# simple-loop.net
KiCad netlist of a schematic drawn in EAGLE
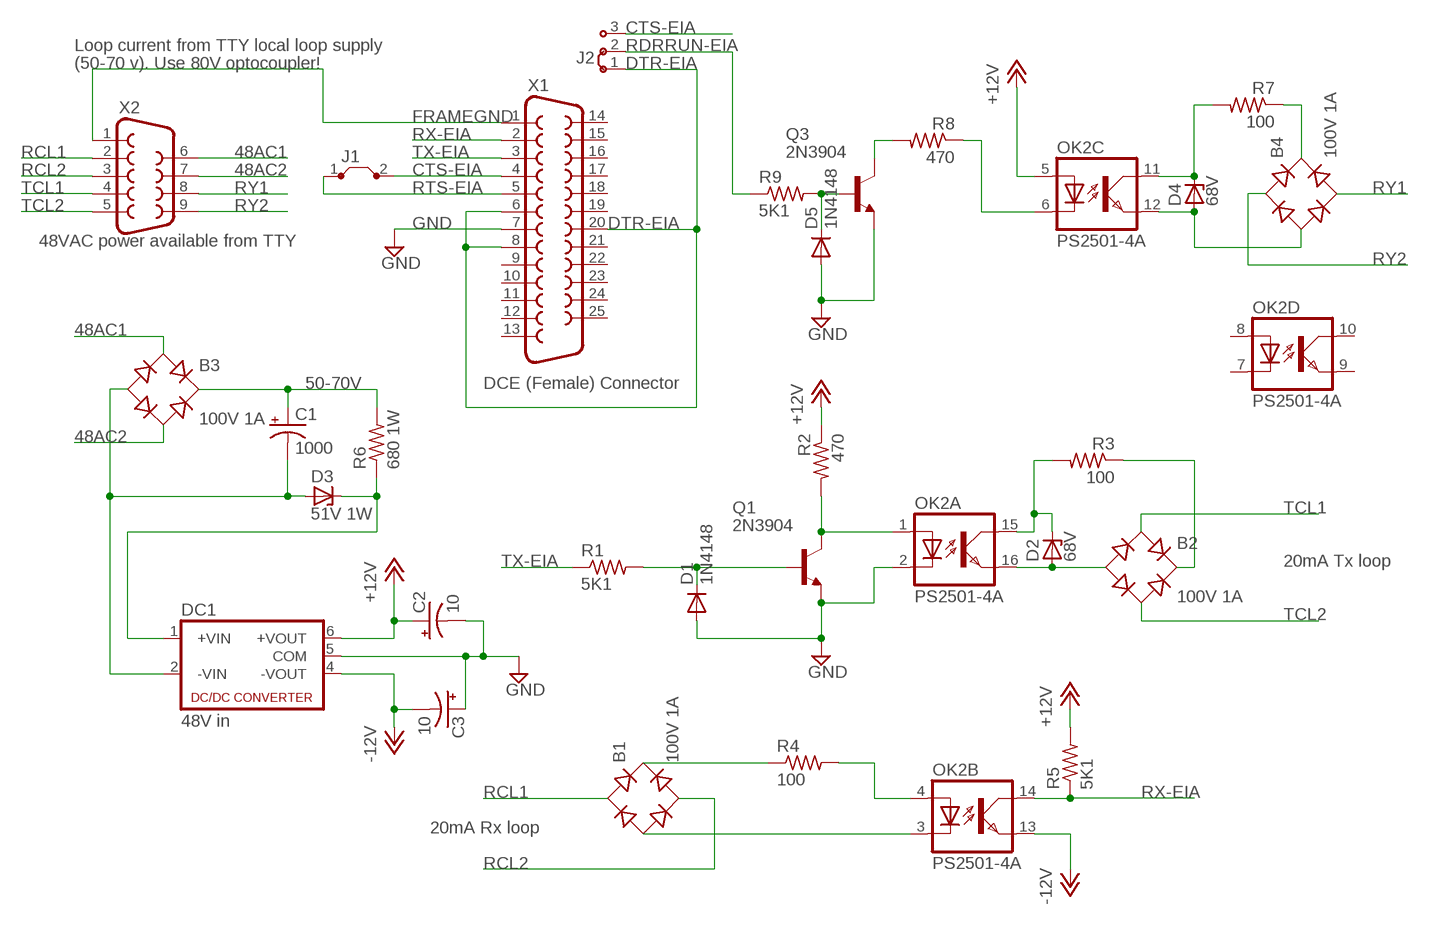
[diagram p0: schematic, sheet 1]

(export (version "E")
  (design (tool "Eeschema 10.0.6"))
  (components
    (comp (ref "B1")
      (value "100V 1A")
      (footprint "eagle-import:RB1A")
      (libsource (lib "eagle-import") (part "RB1A"))
    )
    (comp (ref "B2")
      (value "100V 1A")
      (footprint "eagle-import:RB1A")
      (libsource (lib "eagle-import") (part "RB1A"))
    )
    (comp (ref "B3")
      (value "100V 1A")
      (footprint "eagle-import:RB1A")
      (libsource (lib "eagle-import") (part "RB1A"))
    )
    (comp (ref "B4")
      (value "100V 1A")
      (footprint "eagle-import:RB1A")
      (libsource (lib "eagle-import") (part "RB1A"))
    )
    (comp (ref "C1")
      (value "1000")
      (footprint "eagle-import:E7,5-18")
      (libsource (lib "eagle-import") (part "CPOL-USE7.5-18"))
    )
    (comp (ref "C2")
      (value "10")
      (footprint "eagle-import:B45181A")
      (libsource (lib "eagle-import") (part "CPOL-USB45181A"))
    )
    (comp (ref "C3")
      (value "10")
      (footprint "eagle-import:B45181A")
      (libsource (lib "eagle-import") (part "CPOL-USB45181A"))
    )
    (comp (ref "D1")
      (value "1N4148")
      (footprint "eagle-import:DO35-10")
      (libsource (lib "eagle-import") (part "1N4148DO35-10"))
    )
    (comp (ref "D2")
      (value "68V")
      (footprint "eagle-import:DO41Z10")
      (libsource (lib "eagle-import") (part "ZENER-DIODEDO41Z10"))
    )
    (comp (ref "D3")
      (value "51V 1W")
      (footprint "eagle-import:DO41Z10")
      (libsource (lib "eagle-import") (part "ZENER-DIODEDO41Z10"))
    )
    (comp (ref "D4")
      (value "68V")
      (footprint "eagle-import:DO41Z10")
      (libsource (lib "eagle-import") (part "ZENER-DIODEDO41Z10"))
    )
    (comp (ref "D5")
      (value "1N4148")
      (footprint "eagle-import:DO35-10")
      (libsource (lib "eagle-import") (part "1N4148DO35-10"))
    )
    (comp (ref "DC1")
      (value "48V in")
      (footprint "eagle-import:NMA")
      (fields (field (name "MF") "C & D TECHNOLOGIES, INC") (field (name "MPN") "NMA0515SC"))
      (libsource (lib "eagle-import") (part "NMA"))
    )
    (comp (ref "J1")
      (value "J5MM")
      (footprint "eagle-import:05")
      (libsource (lib "eagle-import") (part "J5MM"))
    )
    (comp (ref "J2")
      (value "J2X5MM")
      (footprint "eagle-import:05C")
      (libsource (lib "eagle-import") (part "J2X5MM"))
    )
    (comp (ref "OK2")
      (value "PS2501-4A")
      (footprint "eagle-import:DIL16")
      (fields (field (name "MF") "VISHAY/TELEFUNKEN") (field (name "MPN") "ILQ1"))
      (libsource (lib "eagle-import") (part "ILQ1"))
    )
    (comp (ref "Q1")
      (value "2N3904")
      (footprint "eagle-import:TO92")
      (libsource (lib "eagle-import") (part "2N3904"))
    )
    (comp (ref "Q3")
      (value "2N3904")
      (footprint "eagle-import:TO92")
      (libsource (lib "eagle-import") (part "2N3904"))
    )
    (comp (ref "R1")
      (value "5K1")
      (footprint "eagle-import:0207_10")
      (libsource (lib "eagle-import") (part "R-US_0207/10"))
    )
    (comp (ref "R2")
      (value "470")
      (footprint "eagle-import:0207_10")
      (libsource (lib "eagle-import") (part "R-US_0207/10"))
    )
    (comp (ref "R3")
      (value "100")
      (footprint "eagle-import:0207_10")
      (libsource (lib "eagle-import") (part "R-US_0207/10"))
    )
    (comp (ref "R4")
      (value "100")
      (footprint "eagle-import:0207_10")
      (libsource (lib "eagle-import") (part "R-US_0207/10"))
    )
    (comp (ref "R5")
      (value "5K1")
      (footprint "eagle-import:0207_10")
      (libsource (lib "eagle-import") (part "R-US_0207/10"))
    )
    (comp (ref "R6")
      (value "680 1W")
      (footprint "eagle-import:0617_17")
      (libsource (lib "eagle-import") (part "R-US_0617/17"))
    )
    (comp (ref "R7")
      (value "100")
      (footprint "eagle-import:0207_10")
      (libsource (lib "eagle-import") (part "R-US_0207/10"))
    )
    (comp (ref "R8")
      (value "470")
      (footprint "eagle-import:0207_10")
      (libsource (lib "eagle-import") (part "R-US_0207/10"))
    )
    (comp (ref "R9")
      (value "5K1")
      (footprint "eagle-import:0207_10")
      (libsource (lib "eagle-import") (part "R-US_0207/10"))
    )
    (comp (ref "X1")
      (value "F25H")
      (footprint "eagle-import:F25H")
      (libsource (lib "eagle-import") (part "F25H"))
    )
    (comp (ref "X2")
      (value "F09H")
      (footprint "eagle-import:F09H")
      (libsource (lib "eagle-import") (part "F09H"))
    )
  )
  (nets
    (net (code "1") (name "+12V") (class "Default")
      (node (ref "C2") (pin "+") (pinfunction "+_+") (pintype "passive"))
      (node (ref "DC1") (pin "6") (pinfunction "+VOUT_6") (pintype "passive"))
      (node (ref "OK2") (pin "5") (pinfunction "A_5") (pintype "passive"))
      (node (ref "R2") (pin "1") (pinfunction "1_1") (pintype "passive"))
      (node (ref "R5") (pin "2") (pinfunction "2_2") (pintype "passive"))
    )
    (net (code "2") (name "-12V") (class "Default")
      (node (ref "C3") (pin "-") (pinfunction "-_-") (pintype "passive"))
      (node (ref "DC1") (pin "4") (pinfunction "-VOUT_4") (pintype "passive"))
      (node (ref "OK2") (pin "13") (pinfunction "EMIT_13") (pintype "passive"))
    )
    (net (code "3") (name "/48AC1") (class "Default")
      (node (ref "B3") (pin "AC1") (pinfunction "AC1_AC1") (pintype "passive"))
      (node (ref "X2") (pin "6") (pinfunction "6_6") (pintype "passive"))
    )
    (net (code "4") (name "/48AC2") (class "Default")
      (node (ref "B3") (pin "AC2") (pinfunction "AC2_AC2") (pintype "passive"))
      (node (ref "X2") (pin "7") (pinfunction "7_7") (pintype "passive"))
    )
    (net (code "5") (name "/50-70V") (class "Default")
      (node (ref "B3") (pin "+") (pinfunction "+_+") (pintype "passive"))
      (node (ref "C1") (pin "+") (pinfunction "+_+") (pintype "passive"))
      (node (ref "R6") (pin "2") (pinfunction "2_2") (pintype "passive"))
    )
    (net (code "6") (name "/CTS-EIA") (class "Default")
      (node (ref "J1") (pin "2") (pinfunction "2_2") (pintype "passive"))
      (node (ref "J2") (pin "3") (pinfunction "3_3") (pintype "passive"))
      (node (ref "X1") (pin "4") (pinfunction "4_4") (pintype "passive"))
    )
    (net (code "7") (name "/DTR-EIA") (class "Default")
      (node (ref "J2") (pin "1") (pinfunction "1_1") (pintype "passive"))
      (node (ref "X1") (pin "20") (pinfunction "20_20") (pintype "passive"))
      (node (ref "X1") (pin "6") (pinfunction "6_6") (pintype "passive"))
      (node (ref "X1") (pin "8") (pinfunction "8_8") (pintype "passive"))
    )
    (net (code "8") (name "/FRAMEGND") (class "Default")
      (node (ref "X1") (pin "1") (pinfunction "1_1") (pintype "passive"))
      (node (ref "X2") (pin "1") (pinfunction "1_1") (pintype "passive"))
    )
    (net (code "9") (name "/RCL1") (class "Default")
      (node (ref "B1") (pin "AC1") (pinfunction "AC1_AC1") (pintype "passive"))
      (node (ref "X2") (pin "2") (pinfunction "2_2") (pintype "passive"))
    )
    (net (code "10") (name "/RCL2") (class "Default")
      (node (ref "B1") (pin "AC2") (pinfunction "AC2_AC2") (pintype "passive"))
      (node (ref "X2") (pin "3") (pinfunction "3_3") (pintype "passive"))
    )
    (net (code "11") (name "/RDRRUN-EIA") (class "Default")
      (node (ref "J2") (pin "2") (pinfunction "2_2") (pintype "passive"))
      (node (ref "R9") (pin "1") (pinfunction "1_1") (pintype "passive"))
    )
    (net (code "12") (name "/RTS-EIA") (class "Default")
      (node (ref "J1") (pin "1") (pinfunction "1_1") (pintype "passive"))
      (node (ref "X1") (pin "5") (pinfunction "5_5") (pintype "passive"))
    )
    (net (code "13") (name "/RX-EIA") (class "Default")
      (node (ref "OK2") (pin "14") (pinfunction "COL_14") (pintype "passive"))
      (node (ref "R5") (pin "1") (pinfunction "1_1") (pintype "passive"))
      (node (ref "X1") (pin "2") (pinfunction "2_2") (pintype "passive"))
    )
    (net (code "14") (name "/RY1") (class "Default")
      (node (ref "B4") (pin "AC2") (pinfunction "AC2_AC2") (pintype "passive"))
      (node (ref "X2") (pin "8") (pinfunction "8_8") (pintype "passive"))
    )
    (net (code "15") (name "/RY2") (class "Default")
      (node (ref "B4") (pin "AC1") (pinfunction "AC1_AC1") (pintype "passive"))
      (node (ref "X2") (pin "9") (pinfunction "9_9") (pintype "passive"))
    )
    (net (code "16") (name "/TCL1") (class "Default")
      (node (ref "B2") (pin "AC1") (pinfunction "AC1_AC1") (pintype "passive"))
      (node (ref "X2") (pin "4") (pinfunction "4_4") (pintype "passive"))
    )
    (net (code "17") (name "/TCL2") (class "Default")
      (node (ref "B2") (pin "AC2") (pinfunction "AC2_AC2") (pintype "passive"))
      (node (ref "X2") (pin "5") (pinfunction "5_5") (pintype "passive"))
    )
    (net (code "18") (name "/TX-EIA") (class "Default")
      (node (ref "R1") (pin "1") (pinfunction "1_1") (pintype "passive"))
      (node (ref "X1") (pin "3") (pinfunction "3_3") (pintype "passive"))
    )
    (net (code "19") (name "GND") (class "Default")
      (node (ref "C2") (pin "-") (pinfunction "-_-") (pintype "passive"))
      (node (ref "C3") (pin "+") (pinfunction "+_+") (pintype "passive"))
      (node (ref "D1") (pin "A") (pinfunction "A_A") (pintype "passive"))
      (node (ref "D5") (pin "A") (pinfunction "A_A") (pintype "passive"))
      (node (ref "DC1") (pin "5") (pinfunction "COM_5") (pintype "passive"))
      (node (ref "OK2") (pin "2") (pinfunction "C_2") (pintype "passive"))
      (node (ref "Q1") (pin "3") (pinfunction "E_3") (pintype "passive"))
      (node (ref "Q3") (pin "3") (pinfunction "E_3") (pintype "passive"))
      (node (ref "X1") (pin "7") (pinfunction "7_7") (pintype "passive"))
    )
    (net (code "20") (name "Net-(B1-Pad+)") (class "Default")
      (node (ref "B1") (pin "+") (pinfunction "+_+") (pintype "passive"))
      (node (ref "R4") (pin "1") (pinfunction "1_1") (pintype "passive"))
    )
    (net (code "21") (name "Net-(B2-Pad+)") (class "Default")
      (node (ref "B2") (pin "+") (pinfunction "+_+") (pintype "passive"))
      (node (ref "R3") (pin "1") (pinfunction "1_1") (pintype "passive"))
    )
    (net (code "22") (name "Net-(B4-Pad+)") (class "Default")
      (node (ref "B4") (pin "+") (pinfunction "+_+") (pintype "passive"))
      (node (ref "R7") (pin "1") (pinfunction "1_1") (pintype "passive"))
    )
    (net (code "23") (name "Net-(DC1-+VIN)") (class "Default")
      (node (ref "D3") (pin "C") (pinfunction "C_C") (pintype "passive"))
      (node (ref "DC1") (pin "1") (pinfunction "+VIN_1") (pintype "passive"))
      (node (ref "R6") (pin "1") (pinfunction "1_1") (pintype "passive"))
    )
    (net (code "24") (name "Net-(DC1--VIN)") (class "Default")
      (node (ref "B3") (pin "-") (pinfunction "-_-") (pintype "passive"))
      (node (ref "C1") (pin "-") (pinfunction "-_-") (pintype "passive"))
      (node (ref "D3") (pin "A") (pinfunction "A_A") (pintype "passive"))
      (node (ref "DC1") (pin "2") (pinfunction "-VIN_2") (pintype "passive"))
    )
    (net (code "25") (name "Net-(OK2A-A)") (class "Default")
      (node (ref "OK2") (pin "1") (pinfunction "A_1") (pintype "passive"))
      (node (ref "Q1") (pin "1") (pinfunction "C_1") (pintype "passive"))
      (node (ref "R2") (pin "2") (pinfunction "2_2") (pintype "passive"))
    )
    (net (code "26") (name "Net-(OK2A-COL)") (class "Default")
      (node (ref "D2") (pin "C") (pinfunction "C_C") (pintype "passive"))
      (node (ref "OK2") (pin "15") (pinfunction "COL_15") (pintype "passive"))
      (node (ref "R3") (pin "2") (pinfunction "2_2") (pintype "passive"))
    )
    (net (code "27") (name "Net-(OK2A-EMIT)") (class "Default")
      (node (ref "B2") (pin "-") (pinfunction "-_-") (pintype "passive"))
      (node (ref "D2") (pin "A") (pinfunction "A_A") (pintype "passive"))
      (node (ref "OK2") (pin "16") (pinfunction "EMIT_16") (pintype "passive"))
    )
    (net (code "28") (name "Net-(OK2B-A)") (class "Default")
      (node (ref "OK2") (pin "4") (pinfunction "A_4") (pintype "passive"))
      (node (ref "R4") (pin "2") (pinfunction "2_2") (pintype "passive"))
    )
    (net (code "29") (name "Net-(OK2B-C)") (class "Default")
      (node (ref "B1") (pin "-") (pinfunction "-_-") (pintype "passive"))
      (node (ref "OK2") (pin "3") (pinfunction "C_3") (pintype "passive"))
    )
    (net (code "30") (name "Net-(OK2C-C)") (class "Default")
      (node (ref "OK2") (pin "6") (pinfunction "C_6") (pintype "passive"))
      (node (ref "R8") (pin "1") (pinfunction "1_1") (pintype "passive"))
    )
    (net (code "31") (name "Net-(OK2C-COL)") (class "Default")
      (node (ref "D4") (pin "C") (pinfunction "C_C") (pintype "passive"))
      (node (ref "OK2") (pin "11") (pinfunction "COL_11") (pintype "passive"))
      (node (ref "R7") (pin "2") (pinfunction "2_2") (pintype "passive"))
    )
    (net (code "32") (name "Net-(OK2C-EMIT)") (class "Default")
      (node (ref "B4") (pin "-") (pinfunction "-_-") (pintype "passive"))
      (node (ref "D4") (pin "A") (pinfunction "A_A") (pintype "passive"))
      (node (ref "OK2") (pin "12") (pinfunction "EMIT_12") (pintype "passive"))
    )
    (net (code "33") (name "Net-(Q1-B)") (class "Default")
      (node (ref "D1") (pin "C") (pinfunction "C_C") (pintype "passive"))
      (node (ref "Q1") (pin "2") (pinfunction "B_2") (pintype "passive"))
      (node (ref "R1") (pin "2") (pinfunction "2_2") (pintype "passive"))
    )
    (net (code "34") (name "Net-(Q3-B)") (class "Default")
      (node (ref "D5") (pin "C") (pinfunction "C_C") (pintype "passive"))
      (node (ref "Q3") (pin "2") (pinfunction "B_2") (pintype "passive"))
      (node (ref "R9") (pin "2") (pinfunction "2_2") (pintype "passive"))
    )
    (net (code "35") (name "Net-(Q3-C)") (class "Default")
      (node (ref "Q3") (pin "1") (pinfunction "C_1") (pintype "passive"))
      (node (ref "R8") (pin "2") (pinfunction "2_2") (pintype "passive"))
    )
    (net (code "36") (name "unconnected-(OK2D-A-Pad8)") (class "Default")
      (node (ref "OK2") (pin "8") (pinfunction "A_8") (pintype "passive"))
    )
    (net (code "37") (name "unconnected-(OK2D-C-Pad7)") (class "Default")
      (node (ref "OK2") (pin "7") (pinfunction "C_7") (pintype "passive"))
    )
    (net (code "38") (name "unconnected-(OK2D-COL-Pad10)") (class "Default")
      (node (ref "OK2") (pin "10") (pinfunction "COL_10") (pintype "passive"))
    )
    (net (code "39") (name "unconnected-(OK2D-EMIT-Pad9)") (class "Default")
      (node (ref "OK2") (pin "9") (pinfunction "EMIT_9") (pintype "passive"))
    )
    (net (code "40") (name "unconnected-(X1-Pad9)") (class "Default")
      (node (ref "X1") (pin "9") (pinfunction "9_9") (pintype "passive"))
    )
    (net (code "41") (name "unconnected-(X1-Pad10)") (class "Default")
      (node (ref "X1") (pin "10") (pinfunction "10_10") (pintype "passive"))
    )
    (net (code "42") (name "unconnected-(X1-Pad11)") (class "Default")
      (node (ref "X1") (pin "11") (pinfunction "11_11") (pintype "passive"))
    )
    (net (code "43") (name "unconnected-(X1-Pad12)") (class "Default")
      (node (ref "X1") (pin "12") (pinfunction "12_12") (pintype "passive"))
    )
    (net (code "44") (name "unconnected-(X1-Pad13)") (class "Default")
      (node (ref "X1") (pin "13") (pinfunction "13_13") (pintype "passive"))
    )
    (net (code "45") (name "unconnected-(X1-Pad14)") (class "Default")
      (node (ref "X1") (pin "14") (pinfunction "14_14") (pintype "passive"))
    )
    (net (code "46") (name "unconnected-(X1-Pad15)") (class "Default")
      (node (ref "X1") (pin "15") (pinfunction "15_15") (pintype "passive"))
    )
    (net (code "47") (name "unconnected-(X1-Pad16)") (class "Default")
      (node (ref "X1") (pin "16") (pinfunction "16_16") (pintype "passive"))
    )
    (net (code "48") (name "unconnected-(X1-Pad17)") (class "Default")
      (node (ref "X1") (pin "17") (pinfunction "17_17") (pintype "passive"))
    )
    (net (code "49") (name "unconnected-(X1-Pad18)") (class "Default")
      (node (ref "X1") (pin "18") (pinfunction "18_18") (pintype "passive"))
    )
    (net (code "50") (name "unconnected-(X1-Pad19)") (class "Default")
      (node (ref "X1") (pin "19") (pinfunction "19_19") (pintype "passive"))
    )
    (net (code "51") (name "unconnected-(X1-Pad21)") (class "Default")
      (node (ref "X1") (pin "21") (pinfunction "21_21") (pintype "passive"))
    )
    (net (code "52") (name "unconnected-(X1-Pad22)") (class "Default")
      (node (ref "X1") (pin "22") (pinfunction "22_22") (pintype "passive"))
    )
    (net (code "53") (name "unconnected-(X1-Pad23)") (class "Default")
      (node (ref "X1") (pin "23") (pinfunction "23_23") (pintype "passive"))
    )
    (net (code "54") (name "unconnected-(X1-Pad24)") (class "Default")
      (node (ref "X1") (pin "24") (pinfunction "24_24") (pintype "passive"))
    )
    (net (code "55") (name "unconnected-(X1-Pad25)") (class "Default")
      (node (ref "X1") (pin "25") (pinfunction "25_25") (pintype "passive"))
    )
  )
)
